# 3_3VRegulator.net
KiCad netlist of a schematic drawn in Altium Designer
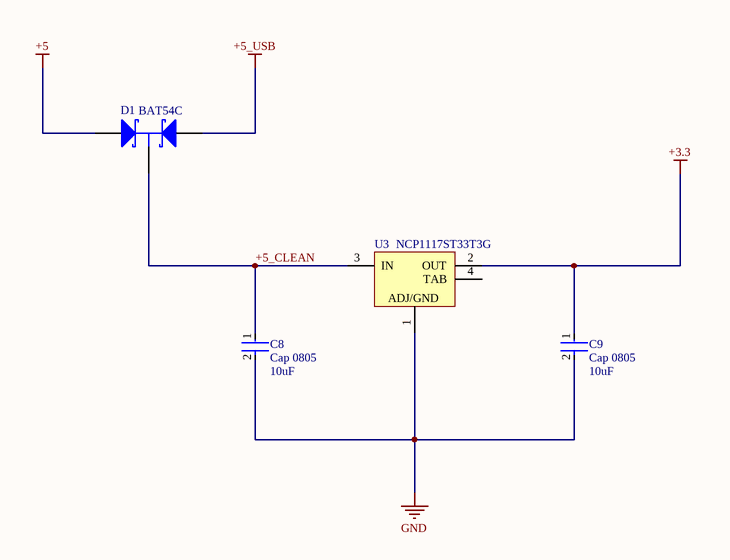
[diagram p0: 3_3VRegulator.SchDoc]

(export (version "E")
  (design (tool "Eeschema 10.0.6"))
  (components
    (comp (ref "C8")
      (value "Cap 0805")
      (footprint "FP-GRM216-0_1-IPC_C")
      (description "Capacitor")
      (fields (field (name "ALTIUM_VALUE") "10uF"))
      (libsource (lib "Altium Content Vault") (part "236180d848d6139a670b325ea6854c9"))
    )
    (comp (ref "C9")
      (value "Cap 0805")
      (footprint "FP-GRM216-0_1-IPC_C")
      (description "Capacitor")
      (fields (field (name "ALTIUM_VALUE") "10uF"))
      (libsource (lib "Altium Content Vault") (part "236180d848d6139a670b325ea6854c9"))
    )
    (comp (ref "D1")
      (value "BAT54C")
      (footprint "NXP-SOT23-3_V")
      (description "Schottky Barrier Diode, 30 V, 2 uA, -55 to 150 degC, 3-Pin SOT23, RoHS, Tape and Reel")
      (fields (field (name "MANUFACTURER") "NXP Semiconductors"))
      (libsource (lib "Altium Content Vault") (part "NXP-DSKY_A1A2K3-3"))
    )
    (comp (ref "U3")
      (value "NCP1117ST33T3G")
      (footprint "ONSC-SOT-223-4-318H-01_A_V")
      (fields (field (name "TOLERANCE") "1%"))
      (libsource (lib "Altium Content Vault") (part "ONSC-NCP1117-SOT223-4"))
    )
  )
  (nets
    (net (code "1") (name "+3.3") (class "Default")
      (node (ref "C9") (pin "1") (pinfunction "1_1") (pintype "passive"))
      (node (ref "U3") (pin "2") (pinfunction "OUT_2") (pintype "power_in"))
    )
    (net (code "2") (name "+5") (class "Default")
      (node (ref "D1") (pin "2") (pinfunction "A_2") (pintype "passive"))
    )
    (net (code "3") (name "+5_USB") (class "Default")
      (node (ref "D1") (pin "1") (pinfunction "A_1") (pintype "passive"))
    )
    (net (code "4") (name "/+5_CLEAN") (class "Default")
      (node (ref "C8") (pin "1") (pinfunction "1_1") (pintype "passive"))
      (node (ref "D1") (pin "3") (pinfunction "K_3") (pintype "passive"))
      (node (ref "U3") (pin "3") (pinfunction "IN_3") (pintype "power_in"))
    )
    (net (code "5") (name "GND") (class "Default")
      (node (ref "C8") (pin "2") (pinfunction "2_2") (pintype "passive"))
      (node (ref "C9") (pin "2") (pinfunction "2_2") (pintype "passive"))
      (node (ref "U3") (pin "1") (pinfunction "ADJ/GND_1") (pintype "passive"))
    )
    (net (code "6") (name "unconnected-(U3-TAB-Pad4)") (class "Default")
      (node (ref "U3") (pin "4") (pinfunction "TAB_4") (pintype "passive"))
    )
  )
)
